# PWR_LTM4622.net
KiCad netlist of a schematic drawn in Altium Designer
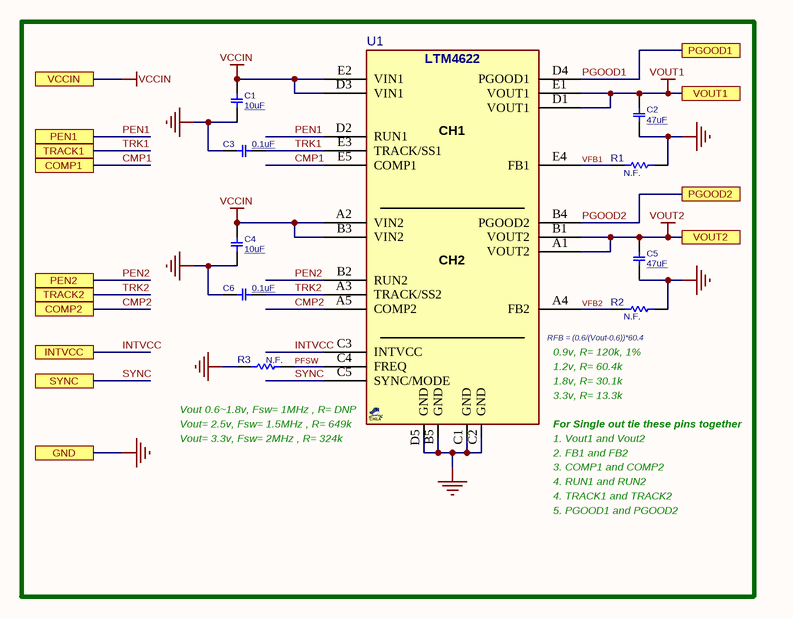
[diagram p0: PWR_LTM4622.SchDoc]

(export (version "E")
  (design (tool "Eeschema 10.0.6"))
  (components
    (comp (ref "C1")
      (value "10uF")
      (footprint "C0805")
      (description "CAP, MLCC")
      (libsource (lib "passive_smd") (part "CAP_SMD_MLCC"))
    )
    (comp (ref "C2")
      (value "47uF")
      (footprint "C0805")
      (description "CAP, MLCC")
      (libsource (lib "passive_smd") (part "CAP_SMD_MLCC"))
    )
    (comp (ref "C3")
      (value "0.1uF")
      (footprint "C0402")
      (description "CAP, MLCC")
      (libsource (lib "passive_smd") (part "CAP_SMD_MLCC"))
    )
    (comp (ref "C4")
      (value "10uF")
      (footprint "C0805")
      (description "CAP, MLCC")
      (libsource (lib "passive_smd") (part "CAP_SMD_MLCC"))
    )
    (comp (ref "C5")
      (value "47uF")
      (footprint "C0805")
      (description "CAP, MLCC")
      (libsource (lib "passive_smd") (part "CAP_SMD_MLCC"))
    )
    (comp (ref "C6")
      (value "0.1uF")
      (footprint "C0402")
      (description "CAP, MLCC")
      (libsource (lib "passive_smd") (part "CAP_SMD_MLCC"))
    )
    (comp (ref "R1")
      (value "N.F.")
      (footprint "R0402")
      (description "RESISTOR, SMD")
      (libsource (lib "passive_smd") (part "RES_SMD"))
    )
    (comp (ref "R2")
      (value "N.F.")
      (footprint "R0402")
      (description "RESISTOR, SMD")
      (libsource (lib "passive_smd") (part "RES_SMD"))
    )
    (comp (ref "R3")
      (value "N.F.")
      (footprint "R0402")
      (description "RESISTOR, SMD")
      (libsource (lib "passive_smd") (part "RES_SMD"))
    )
    (comp (ref "U1")
      (value "LTM4622")
      (footprint "BGA127_25_6262")
      (description "DC2DC Switching MODULE, Dual, 2.5A")
      (fields (field (name "MANF") "Analog Devices") (field (name "MANF_P#") "LTM4622EY, LTM4622IY"))
      (libsource (lib "pwr_switching_module") (part "LTM4622_BGA25"))
    )
  )
  (nets
    (net (code "1") (name "/CMP1") (class "Default")
      (node (ref "U1") (pin "E5") (pinfunction "COMP1_E5") (pintype "passive"))
    )
    (net (code "2") (name "/CMP2") (class "Default")
      (node (ref "U1") (pin "A5") (pinfunction "COMP2_A5") (pintype "passive"))
    )
    (net (code "3") (name "/INTVCC") (class "Default")
      (node (ref "U1") (pin "C3") (pinfunction "INTVCC_C3") (pintype "passive"))
    )
    (net (code "4") (name "/PEN1") (class "Default")
      (node (ref "U1") (pin "D2") (pinfunction "RUN1_D2") (pintype "passive"))
    )
    (net (code "5") (name "/PEN2") (class "Default")
      (node (ref "U1") (pin "B2") (pinfunction "RUN2_B2") (pintype "passive"))
    )
    (net (code "6") (name "/PFSW") (class "Default")
      (node (ref "R3") (pin "1") (pinfunction "1_1") (pintype "passive"))
      (node (ref "U1") (pin "C4") (pinfunction "FREQ_C4") (pintype "passive"))
    )
    (net (code "7") (name "/PGOOD1") (class "Default")
      (node (ref "U1") (pin "D4") (pinfunction "PGOOD1_D4") (pintype "passive"))
    )
    (net (code "8") (name "/PGOOD2") (class "Default")
      (node (ref "U1") (pin "B4") (pinfunction "PGOOD2_B4") (pintype "passive"))
    )
    (net (code "9") (name "/SYNC") (class "Default")
      (node (ref "U1") (pin "C5") (pinfunction "SYNC/MODE_C5") (pintype "passive"))
    )
    (net (code "10") (name "/TRK1") (class "Default")
      (node (ref "C3") (pin "2") (pinfunction "2_2") (pintype "passive"))
      (node (ref "U1") (pin "E3") (pinfunction "TRACK/SS1_E3") (pintype "passive"))
    )
    (net (code "11") (name "/TRK2") (class "Default")
      (node (ref "C6") (pin "2") (pinfunction "2_2") (pintype "passive"))
      (node (ref "U1") (pin "A3") (pinfunction "TRACK/SS2_A3") (pintype "passive"))
    )
    (net (code "12") (name "/VFB1") (class "Default")
      (node (ref "R1") (pin "2") (pinfunction "2_2") (pintype "passive"))
      (node (ref "U1") (pin "E4") (pinfunction "FB1_E4") (pintype "passive"))
    )
    (net (code "13") (name "/VFB2") (class "Default")
      (node (ref "R2") (pin "2") (pinfunction "2_2") (pintype "passive"))
      (node (ref "U1") (pin "A4") (pinfunction "FB2_A4") (pintype "passive"))
    )
    (net (code "14") (name "GND") (class "Default")
      (node (ref "C1") (pin "2") (pinfunction "2_2") (pintype "passive"))
      (node (ref "C2") (pin "2") (pinfunction "2_2") (pintype "passive"))
      (node (ref "C3") (pin "1") (pinfunction "1_1") (pintype "passive"))
      (node (ref "C4") (pin "2") (pinfunction "2_2") (pintype "passive"))
      (node (ref "C5") (pin "2") (pinfunction "2_2") (pintype "passive"))
      (node (ref "C6") (pin "1") (pinfunction "1_1") (pintype "passive"))
      (node (ref "R1") (pin "1") (pinfunction "1_1") (pintype "passive"))
      (node (ref "R2") (pin "1") (pinfunction "1_1") (pintype "passive"))
      (node (ref "R3") (pin "2") (pinfunction "2_2") (pintype "passive"))
      (node (ref "U1") (pin "B5") (pinfunction "GND_B5") (pintype "passive"))
      (node (ref "U1") (pin "C1") (pinfunction "GND_C1") (pintype "passive"))
      (node (ref "U1") (pin "C2") (pinfunction "GND_C2") (pintype "passive"))
      (node (ref "U1") (pin "D5") (pinfunction "GND_D5") (pintype "passive"))
    )
    (net (code "15") (name "VCCIN") (class "Default")
      (node (ref "C1") (pin "1") (pinfunction "1_1") (pintype "passive"))
      (node (ref "C4") (pin "1") (pinfunction "1_1") (pintype "passive"))
      (node (ref "U1") (pin "A2") (pinfunction "VIN2_A2") (pintype "passive"))
      (node (ref "U1") (pin "B3") (pinfunction "VIN2_B3") (pintype "passive"))
      (node (ref "U1") (pin "D3") (pinfunction "VIN1_D3") (pintype "passive"))
      (node (ref "U1") (pin "E2") (pinfunction "VIN1_E2") (pintype "passive"))
    )
    (net (code "16") (name "VOUT1") (class "Default")
      (node (ref "C2") (pin "1") (pinfunction "1_1") (pintype "passive"))
      (node (ref "U1") (pin "D1") (pinfunction "VOUT1_D1") (pintype "passive"))
      (node (ref "U1") (pin "E1") (pinfunction "VOUT1_E1") (pintype "passive"))
    )
    (net (code "17") (name "VOUT2") (class "Default")
      (node (ref "C5") (pin "1") (pinfunction "1_1") (pintype "passive"))
      (node (ref "U1") (pin "A1") (pinfunction "VOUT2_A1") (pintype "passive"))
      (node (ref "U1") (pin "B1") (pinfunction "VOUT2_B1") (pintype "passive"))
    )
  )
)
